# ESC.net
KiCad netlist of a schematic drawn in Altium Designer
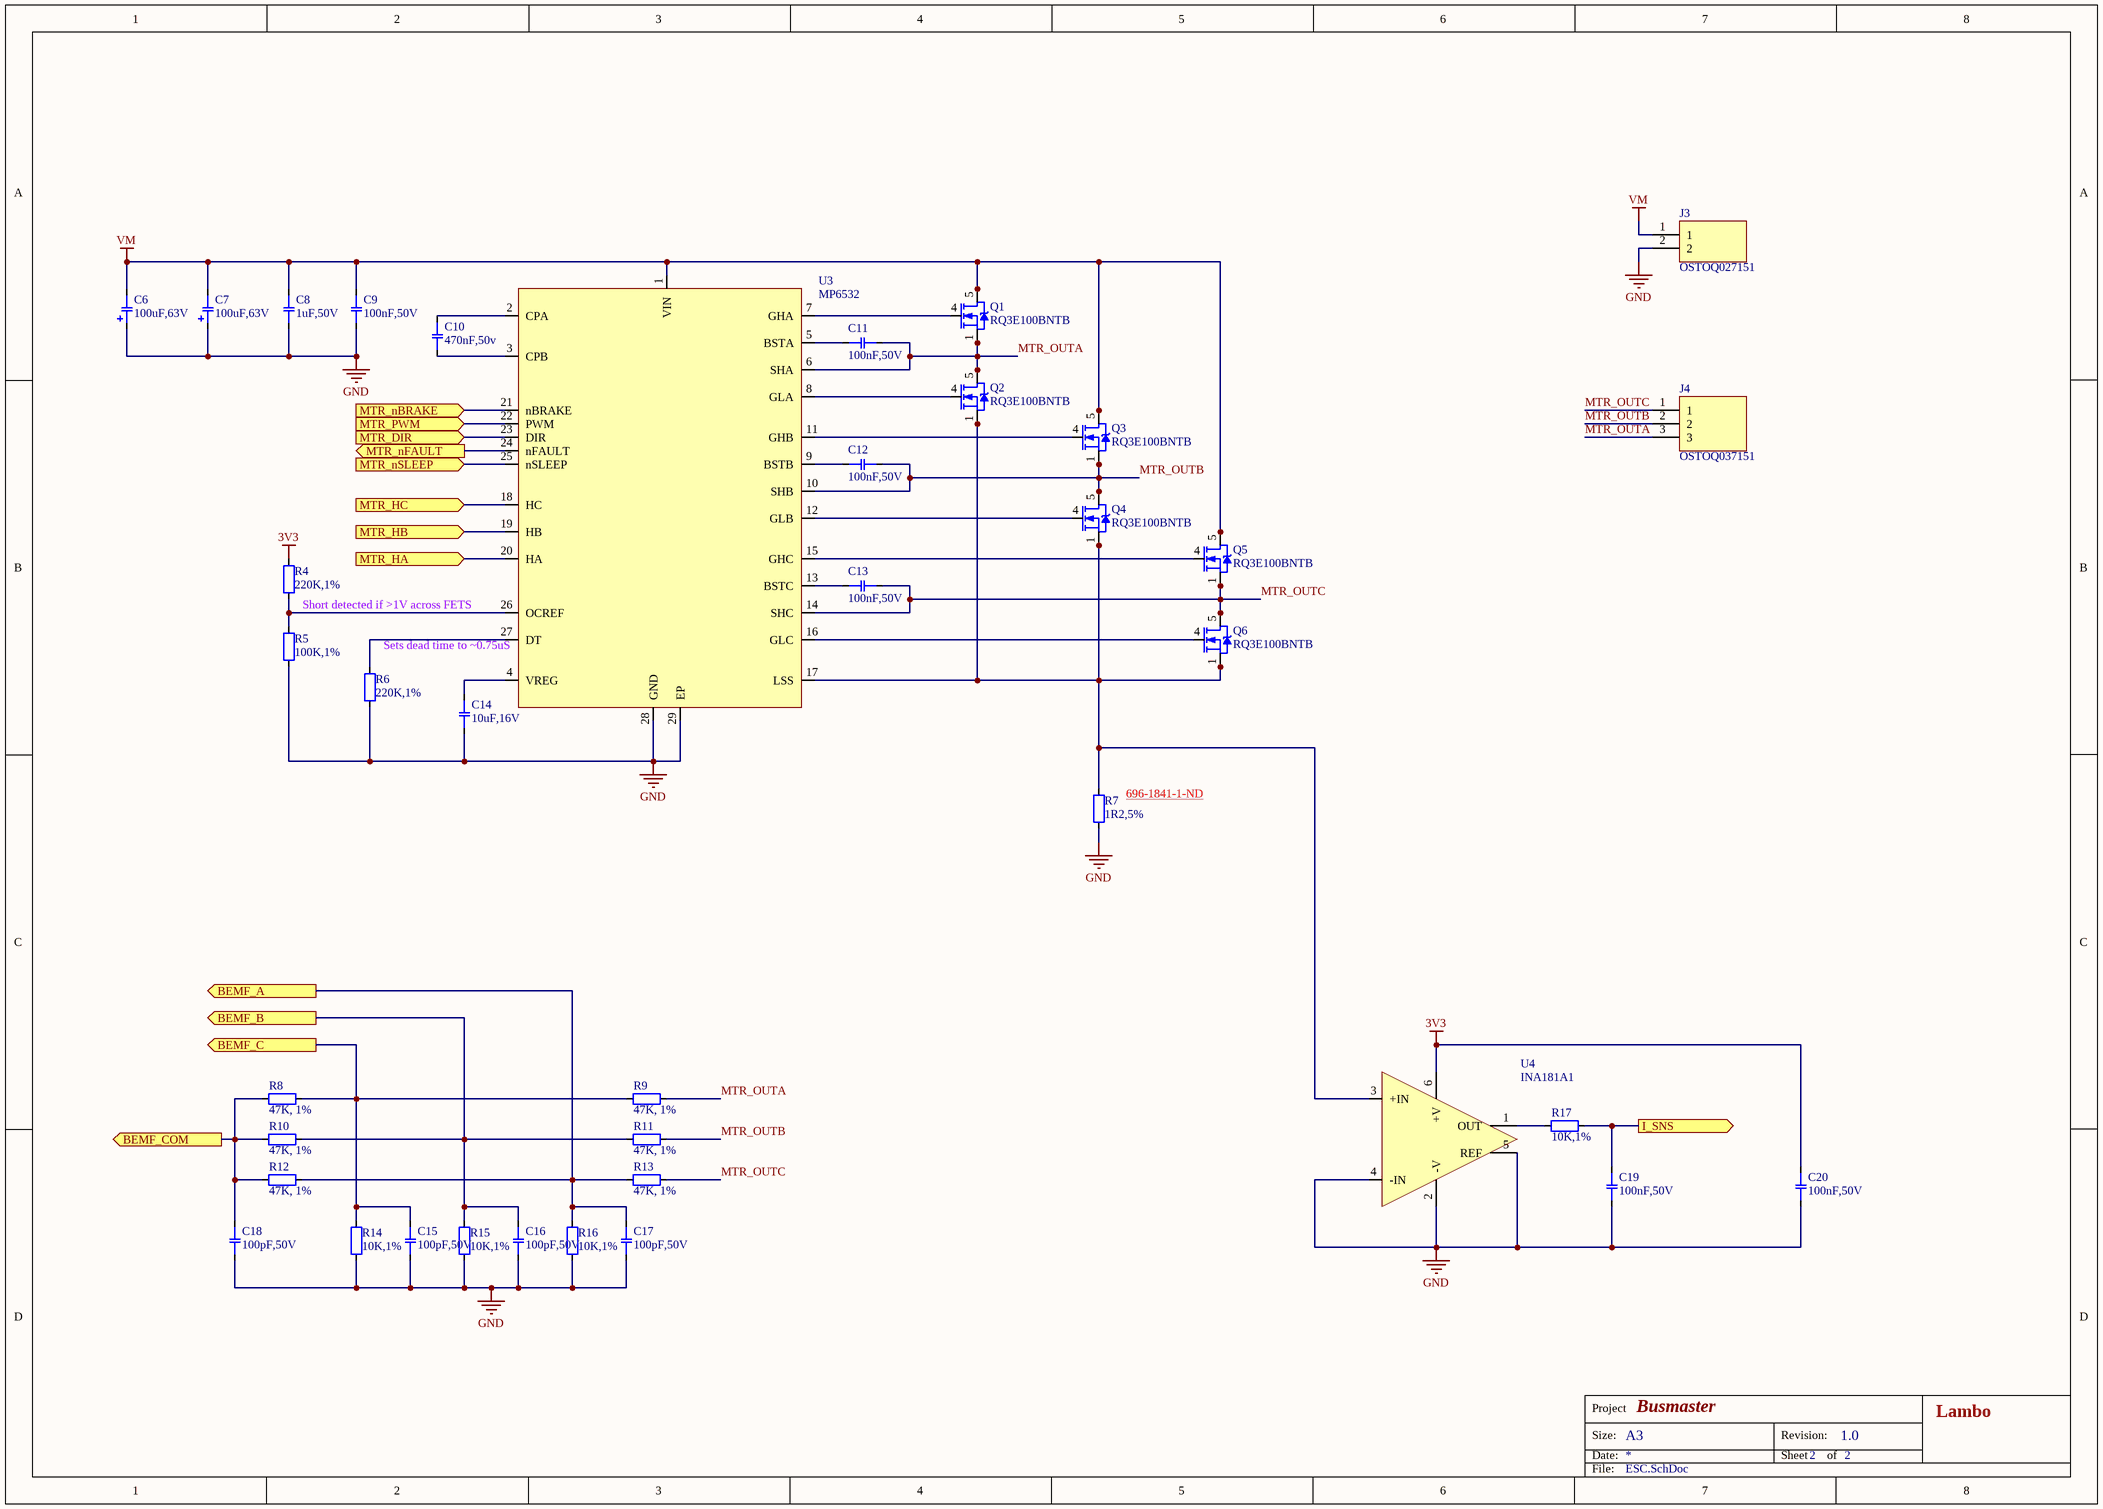
[diagram p0: ESC.SchDoc]

(export (version "E")
  (design (tool "Eeschema 10.0.6"))
  (components
    (comp (ref "C6")
      (value "100uF,63V")
      (footprint "CAPAE1030X1020N")
      (description "CAP ALUM 100UF 63V 20% SMD")
      (fields
        (field (name "MANUFACTURER") "Panasonic Electronic Components")
        (field (name "TOLERANCE") "20%")
      )
      (libsource (lib "library") (part "CAP-POL_1"))
    )
    (comp (ref "C7")
      (value "100uF,63V")
      (footprint "CAPAE1030X1020N")
      (description "CAP ALUM 100UF 63V 20% SMD")
      (fields
        (field (name "MANUFACTURER") "Panasonic Electronic Components")
        (field (name "TOLERANCE") "20%")
      )
      (libsource (lib "library") (part "CAP-POL_1"))
    )
    (comp (ref "C8")
      (value "1uF,50V")
      (footprint "CAPC1608X09N_0603")
      (description "AUTOMOTIVE CAP CER 1UF 50V 10% X5R 0603")
      (fields (field (name "MANUFACTURER") "TDK Corporation") (field (name "TOLERANCE") "10%"))
      (libsource (lib "library") (part "CAP-NP_1"))
    )
    (comp (ref "C9")
      (value "100nF,50V")
      (footprint "CAPC1608X09N_0603")
      (description "CAP CER 0.1UF 50V 10% X7R 0603")
      (fields (field (name "MANUFACTURER") "Kemet") (field (name "TOLERANCE") "10%"))
      (libsource (lib "library") (part "CAP-NP_1"))
    )
    (comp (ref "C10")
      (value "470nF,50v")
      (footprint "CAPC1608X09N_0603")
      (description "AUTOMOTIVE CAP CER 470nF 50V 10% X5R 0603")
      (fields (field (name "MANUFACTURER") "Taiyo Yuden") (field (name "TOLERANCE") "10%"))
      (libsource (lib "library") (part "CAP-NP_1"))
    )
    (comp (ref "C11")
      (value "100nF,50V")
      (footprint "CAPC1608X09N_0603")
      (description "CAP CER 0.1UF 50V 10% X7R 0603")
      (fields (field (name "MANUFACTURER") "Kemet") (field (name "TOLERANCE") "10%"))
      (libsource (lib "library") (part "CAP-NP_1"))
    )
    (comp (ref "C12")
      (value "100nF,50V")
      (footprint "CAPC1608X09N_0603")
      (description "CAP CER 0.1UF 50V 10% X7R 0603")
      (fields (field (name "MANUFACTURER") "Kemet") (field (name "TOLERANCE") "10%"))
      (libsource (lib "library") (part "CAP-NP_1"))
    )
    (comp (ref "C13")
      (value "100nF,50V")
      (footprint "CAPC1608X09N_0603")
      (description "CAP CER 0.1UF 50V 10% X7R 0603")
      (fields (field (name "MANUFACTURER") "Kemet") (field (name "TOLERANCE") "10%"))
      (libsource (lib "library") (part "CAP-NP_1"))
    )
    (comp (ref "C14")
      (value "10uF,16V")
      (footprint "CAPC2012X12N_0805")
      (description "CAP CER 10µF ±10% 16V X7R 0805")
      (fields
        (field (name "MANUFACTURER") "Samsung Electro-Mechanics America, Inc.")
        (field (name "TOLERANCE") "10%")
      )
      (libsource (lib "library") (part "CAP-NP_1"))
    )
    (comp (ref "C15")
      (value "100pF,50V")
      (footprint "CAPC1608X09N_0603")
      (description "CAP CER 100PF 50V 10% NP0 0603")
      (fields (field (name "MANUFACTURER") "AVX") (field (name "TOLERANCE") "10%"))
      (libsource (lib "library") (part "CAP-NP_1"))
    )
    (comp (ref "C16")
      (value "100pF,50V")
      (footprint "CAPC1608X09N_0603")
      (description "CAP CER 100PF 50V 10% NP0 0603")
      (fields (field (name "MANUFACTURER") "AVX") (field (name "TOLERANCE") "10%"))
      (libsource (lib "library") (part "CAP-NP_1"))
    )
    (comp (ref "C17")
      (value "100pF,50V")
      (footprint "CAPC1608X09N_0603")
      (description "CAP CER 100PF 50V 10% NP0 0603")
      (fields (field (name "MANUFACTURER") "AVX") (field (name "TOLERANCE") "10%"))
      (libsource (lib "library") (part "CAP-NP_1"))
    )
    (comp (ref "C18")
      (value "100pF,50V")
      (footprint "CAPC1608X09N_0603")
      (description "CAP CER 100PF 50V 10% NP0 0603")
      (fields (field (name "MANUFACTURER") "AVX") (field (name "TOLERANCE") "10%"))
      (libsource (lib "library") (part "CAP-NP_1"))
    )
    (comp (ref "C19")
      (value "100nF,50V")
      (footprint "CAPC1608X09N_0603")
      (description "CAP CER 0.1UF 50V 10% X7R 0603")
      (fields (field (name "MANUFACTURER") "Kemet") (field (name "TOLERANCE") "10%"))
      (libsource (lib "library") (part "CAP-NP_1"))
    )
    (comp (ref "C20")
      (value "100nF,50V")
      (footprint "CAPC1608X09N_0603")
      (description "CAP CER 0.1UF 50V 10% X7R 0603")
      (fields (field (name "MANUFACTURER") "Kemet") (field (name "TOLERANCE") "10%"))
      (libsource (lib "library") (part "CAP-NP_1"))
    )
    (comp (ref "J3")
      (value "OSTOQ027151")
      (footprint "ONSHORE_OSTOQ027151")
      (description "TERM BLOCK HDR 2POS R/A 5MM")
      (fields (field (name "MANUFACTURER") "On Shore Technology Inc"))
      (libsource (lib "library") (part "ONSHORE_OSTOQ027151"))
    )
    (comp (ref "J4")
      (value "OSTOQ037151")
      (footprint "ONSHORE_OSTOQ037151")
      (description "TERM BLOCK HDR 3POS R/A 5MM")
      (fields (field (name "MANUFACTURER") "On Shore Technology Inc"))
      (libsource (lib "library") (part "ONSHORE_OSTOQ037151"))
    )
    (comp (ref "Q1")
      (value "RQ3E100BNTB")
      (footprint "ROHM-HSMT8")
      (description "MOSFET N-CH 30V 10A 8HSMT")
      (fields (field (name "MANUFACTURER") "Rohm Semiconductor"))
      (libsource (lib "library") (part "MOSFET-N-QFN8"))
    )
    (comp (ref "Q2")
      (value "RQ3E100BNTB")
      (footprint "ROHM-HSMT8")
      (description "MOSFET N-CH 30V 10A 8HSMT")
      (fields (field (name "MANUFACTURER") "Rohm Semiconductor"))
      (libsource (lib "library") (part "MOSFET-N-QFN8"))
    )
    (comp (ref "Q3")
      (value "RQ3E100BNTB")
      (footprint "ROHM-HSMT8")
      (description "MOSFET N-CH 30V 10A 8HSMT")
      (fields (field (name "MANUFACTURER") "Rohm Semiconductor"))
      (libsource (lib "library") (part "MOSFET-N-QFN8"))
    )
    (comp (ref "Q4")
      (value "RQ3E100BNTB")
      (footprint "ROHM-HSMT8")
      (description "MOSFET N-CH 30V 10A 8HSMT")
      (fields (field (name "MANUFACTURER") "Rohm Semiconductor"))
      (libsource (lib "library") (part "MOSFET-N-QFN8"))
    )
    (comp (ref "Q5")
      (value "RQ3E100BNTB")
      (footprint "ROHM-HSMT8")
      (description "MOSFET N-CH 30V 10A 8HSMT")
      (fields (field (name "MANUFACTURER") "Rohm Semiconductor"))
      (libsource (lib "library") (part "MOSFET-N-QFN8"))
    )
    (comp (ref "Q6")
      (value "RQ3E100BNTB")
      (footprint "ROHM-HSMT8")
      (description "MOSFET N-CH 30V 10A 8HSMT")
      (fields (field (name "MANUFACTURER") "Rohm Semiconductor"))
      (libsource (lib "library") (part "MOSFET-N-QFN8"))
    )
    (comp (ref "R4")
      (value "220K,1%")
      (footprint "RESC1608X06N_0603")
      (description "RES 220K OHM 1/10W 1% 0603 SMD")
      (fields (field (name "MANUFACTURER") "Yageo") (field (name "POWER") "0.1W"))
      (libsource (lib "library") (part "RESISTOR_1"))
    )
    (comp (ref "R5")
      (value "100K,1%")
      (footprint "RESC1608X06N_0603")
      (description "RES 100K OHM 1/10W 1% 0603 SMD")
      (fields (field (name "MANUFACTURER") "Yageo") (field (name "POWER") "0.1W"))
      (libsource (lib "library") (part "RESISTOR_1"))
    )
    (comp (ref "R6")
      (value "220K,1%")
      (footprint "RESC1608X06N_0603")
      (description "RES 220K OHM 1/10W 1% 0603 SMD")
      (fields (field (name "MANUFACTURER") "Yageo") (field (name "POWER") "0.1W"))
      (libsource (lib "library") (part "RESISTOR_1"))
    )
    (comp (ref "R7")
      (value "1R2,5%")
      (footprint "RESC6432X07N_2512")
      (description "RES SMD 1.2 OHM 5% 3W 2512")
      (fields (field (name "MANUFACTURER") "TE Connectivity Passive Product") (field (name "POWER") "3W"))
      (libsource (lib "library") (part "RESISTOR_1"))
    )
    (comp (ref "R8")
      (value "47K, 1%")
      (footprint "RESC1608X06N_0603")
      (description "AUTOMOTIVE RES 47.0K OHM 1/10W 1% 0603 SMD")
      (fields (field (name "MANUFACTURER") "Vishay Dale") (field (name "POWER") "0.1W"))
      (libsource (lib "") (part "RESISTOR_1_1"))
    )
    (comp (ref "R9")
      (value "47K, 1%")
      (footprint "RESC1608X06N_0603")
      (description "AUTOMOTIVE RES 47.0K OHM 1/10W 1% 0603 SMD")
      (fields (field (name "MANUFACTURER") "Vishay Dale") (field (name "POWER") "0.1W"))
      (libsource (lib "") (part "RESISTOR_1_1"))
    )
    (comp (ref "R10")
      (value "47K, 1%")
      (footprint "RESC1608X06N_0603")
      (description "AUTOMOTIVE RES 47.0K OHM 1/10W 1% 0603 SMD")
      (fields (field (name "MANUFACTURER") "Vishay Dale") (field (name "POWER") "0.1W"))
      (libsource (lib "") (part "RESISTOR_1_1"))
    )
    (comp (ref "R11")
      (value "47K, 1%")
      (footprint "RESC1608X06N_0603")
      (description "AUTOMOTIVE RES 47.0K OHM 1/10W 1% 0603 SMD")
      (fields (field (name "MANUFACTURER") "Vishay Dale") (field (name "POWER") "0.1W"))
      (libsource (lib "") (part "RESISTOR_1_1"))
    )
    (comp (ref "R12")
      (value "47K, 1%")
      (footprint "RESC1608X06N_0603")
      (description "AUTOMOTIVE RES 47.0K OHM 1/10W 1% 0603 SMD")
      (fields (field (name "MANUFACTURER") "Vishay Dale") (field (name "POWER") "0.1W"))
      (libsource (lib "") (part "RESISTOR_1_1"))
    )
    (comp (ref "R13")
      (value "47K, 1%")
      (footprint "RESC1608X06N_0603")
      (description "AUTOMOTIVE RES 47.0K OHM 1/10W 1% 0603 SMD")
      (fields (field (name "MANUFACTURER") "Vishay Dale") (field (name "POWER") "0.1W"))
      (libsource (lib "") (part "RESISTOR_1_1"))
    )
    (comp (ref "R14")
      (value "10K,1%")
      (footprint "RESC1608X06N_0603")
      (description "RES 10.0K OHM 1/10W 1% 0603 SMD")
      (fields (field (name "MANUFACTURER") "Yageo") (field (name "POWER") "0.1W"))
      (libsource (lib "") (part "RESISTOR_1_2"))
    )
    (comp (ref "R15")
      (value "10K,1%")
      (footprint "RESC1608X06N_0603")
      (description "RES 10.0K OHM 1/10W 1% 0603 SMD")
      (fields (field (name "MANUFACTURER") "Yageo") (field (name "POWER") "0.1W"))
      (libsource (lib "") (part "RESISTOR_1_2"))
    )
    (comp (ref "R16")
      (value "10K,1%")
      (footprint "RESC1608X06N_0603")
      (description "RES 10.0K OHM 1/10W 1% 0603 SMD")
      (fields (field (name "MANUFACTURER") "Yageo") (field (name "POWER") "0.1W"))
      (libsource (lib "") (part "RESISTOR_1_2"))
    )
    (comp (ref "R17")
      (value "10K,1%")
      (footprint "RESC1608X06N_0603")
      (description "RES 10.0K OHM 1/10W 1% 0603 SMD")
      (fields (field (name "MANUFACTURER") "Yageo") (field (name "POWER") "0.1W"))
      (libsource (lib "") (part "RESISTOR_1_3"))
    )
    (comp (ref "U3")
      (value "MP6532")
      (footprint "QFN40P400X400X100-28N_28QFN")
      (description "IC MOTOR DRIVER 5V-60V 28QFN")
      (fields
        (field (name "MANUFACTURER") "Monolithic Power Systems Inc.")
        (field (name "MANUFACTURER PART NUMBER") "MP6532-GR-Z")
      )
      (libsource (lib "library") (part "MP6532"))
    )
    (comp (ref "U4")
      (value "INA181A1")
      (footprint "SOT95P280X145-6N_SOT23-6")
      (description "IC AMP CUR SENSE 350KHZ SOT23-6")
      (fields
        (field (name "MANUFACTURER") "Texas Instruments")
        (field (name "MANUFACTURER PART NUMBER") "INA181A1IDBVT")
      )
      (libsource (lib "library") (part "INA181AX"))
    )
  )
  (nets
    (net (code "1") (name "/BEMF_A") (class "Default")
      (node (ref "C17") (pin "2") (pinfunction "2_2") (pintype "passive"))
      (node (ref "R12") (pin "2") (pinfunction "2_2") (pintype "passive"))
      (node (ref "R13") (pin "1") (pinfunction "1_1") (pintype "passive"))
      (node (ref "R16") (pin "1") (pinfunction "1_1") (pintype "passive"))
    )
    (net (code "2") (name "/BEMF_B") (class "Default")
      (node (ref "C16") (pin "2") (pinfunction "2_2") (pintype "passive"))
      (node (ref "R10") (pin "2") (pinfunction "2_2") (pintype "passive"))
      (node (ref "R11") (pin "1") (pinfunction "1_1") (pintype "passive"))
      (node (ref "R15") (pin "1") (pinfunction "1_1") (pintype "passive"))
    )
    (net (code "3") (name "/BEMF_C") (class "Default")
      (node (ref "C15") (pin "2") (pinfunction "2_2") (pintype "passive"))
      (node (ref "R14") (pin "1") (pinfunction "1_1") (pintype "passive"))
      (node (ref "R8") (pin "2") (pinfunction "2_2") (pintype "passive"))
      (node (ref "R9") (pin "1") (pinfunction "1_1") (pintype "passive"))
    )
    (net (code "4") (name "/BEMF_COM") (class "Default")
      (node (ref "C18") (pin "2") (pinfunction "2_2") (pintype "passive"))
      (node (ref "R10") (pin "1") (pinfunction "1_1") (pintype "passive"))
      (node (ref "R12") (pin "1") (pinfunction "1_1") (pintype "passive"))
      (node (ref "R8") (pin "1") (pinfunction "1_1") (pintype "passive"))
    )
    (net (code "5") (name "/I_SNS") (class "Default")
      (node (ref "C19") (pin "1") (pinfunction "1_1") (pintype "passive"))
      (node (ref "R17") (pin "1") (pinfunction "1_1") (pintype "passive"))
    )
    (net (code "6") (name "/MTR_DIR") (class "Default")
      (node (ref "U3") (pin "23") (pinfunction "DIR_23") (pintype "passive"))
    )
    (net (code "7") (name "/MTR_HA") (class "Default")
      (node (ref "U3") (pin "20") (pinfunction "HA_20") (pintype "passive"))
    )
    (net (code "8") (name "/MTR_HB") (class "Default")
      (node (ref "U3") (pin "19") (pinfunction "HB_19") (pintype "passive"))
    )
    (net (code "9") (name "/MTR_HC") (class "Default")
      (node (ref "U3") (pin "18") (pinfunction "HC_18") (pintype "passive"))
    )
    (net (code "10") (name "/MTR_OUTA") (class "Default")
      (node (ref "C11") (pin "1") (pinfunction "1_1") (pintype "passive"))
      (node (ref "J4") (pin "3") (pinfunction "3_3") (pintype "passive"))
      (node (ref "Q1") (pin "1") (pinfunction "S_1") (pintype "passive"))
      (node (ref "Q1") (pin "2") (pinfunction "S_2") (pintype "passive"))
      (node (ref "Q1") (pin "3") (pinfunction "S_3") (pintype "passive"))
      (node (ref "Q2") (pin "5") (pinfunction "D_5") (pintype "passive"))
      (node (ref "Q2") (pin "6") (pinfunction "D_6") (pintype "passive"))
      (node (ref "Q2") (pin "7") (pinfunction "D_7") (pintype "passive"))
      (node (ref "Q2") (pin "8") (pinfunction "D_8") (pintype "passive"))
      (node (ref "R9") (pin "2") (pinfunction "2_2") (pintype "passive"))
      (node (ref "U3") (pin "6") (pinfunction "SHA_6") (pintype "passive"))
    )
    (net (code "11") (name "/MTR_OUTB") (class "Default")
      (node (ref "C12") (pin "1") (pinfunction "1_1") (pintype "passive"))
      (node (ref "J4") (pin "2") (pinfunction "2_2") (pintype "passive"))
      (node (ref "Q3") (pin "1") (pinfunction "S_1") (pintype "passive"))
      (node (ref "Q3") (pin "2") (pinfunction "S_2") (pintype "passive"))
      (node (ref "Q3") (pin "3") (pinfunction "S_3") (pintype "passive"))
      (node (ref "Q4") (pin "5") (pinfunction "D_5") (pintype "passive"))
      (node (ref "Q4") (pin "6") (pinfunction "D_6") (pintype "passive"))
      (node (ref "Q4") (pin "7") (pinfunction "D_7") (pintype "passive"))
      (node (ref "Q4") (pin "8") (pinfunction "D_8") (pintype "passive"))
      (node (ref "R11") (pin "2") (pinfunction "2_2") (pintype "passive"))
      (node (ref "U3") (pin "10") (pinfunction "SHB_10") (pintype "passive"))
    )
    (net (code "12") (name "/MTR_OUTC") (class "Default")
      (node (ref "C13") (pin "1") (pinfunction "1_1") (pintype "passive"))
      (node (ref "J4") (pin "1") (pinfunction "1_1") (pintype "passive"))
      (node (ref "Q5") (pin "1") (pinfunction "S_1") (pintype "passive"))
      (node (ref "Q5") (pin "2") (pinfunction "S_2") (pintype "passive"))
      (node (ref "Q5") (pin "3") (pinfunction "S_3") (pintype "passive"))
      (node (ref "Q6") (pin "5") (pinfunction "D_5") (pintype "passive"))
      (node (ref "Q6") (pin "6") (pinfunction "D_6") (pintype "passive"))
      (node (ref "Q6") (pin "7") (pinfunction "D_7") (pintype "passive"))
      (node (ref "Q6") (pin "8") (pinfunction "D_8") (pintype "passive"))
      (node (ref "R13") (pin "2") (pinfunction "2_2") (pintype "passive"))
      (node (ref "U3") (pin "14") (pinfunction "SHC_14") (pintype "passive"))
    )
    (net (code "13") (name "/MTR_PWM") (class "Default")
      (node (ref "U3") (pin "22") (pinfunction "PWM_22") (pintype "passive"))
    )
    (net (code "14") (name "/MTR_nBRAKE") (class "Default")
      (node (ref "U3") (pin "21") (pinfunction "nBRAKE_21") (pintype "passive"))
    )
    (net (code "15") (name "/MTR_nFAULT") (class "Default")
      (node (ref "U3") (pin "24") (pinfunction "nFAULT_24") (pintype "passive"))
    )
    (net (code "16") (name "/MTR_nSLEEP") (class "Default")
      (node (ref "U3") (pin "25") (pinfunction "nSLEEP_25") (pintype "passive"))
    )
    (net (code "17") (name "3V3") (class "Default")
      (node (ref "C20") (pin "1") (pinfunction "1_1") (pintype "passive"))
      (node (ref "R4") (pin "2") (pinfunction "2_2") (pintype "passive"))
      (node (ref "U4") (pin "6") (pinfunction "+V_6") (pintype "passive"))
    )
    (net (code "18") (name "GND") (class "Default")
      (node (ref "C14") (pin "1") (pinfunction "1_1") (pintype "passive"))
      (node (ref "C15") (pin "1") (pinfunction "1_1") (pintype "passive"))
      (node (ref "C16") (pin "1") (pinfunction "1_1") (pintype "passive"))
      (node (ref "C17") (pin "1") (pinfunction "1_1") (pintype "passive"))
      (node (ref "C18") (pin "1") (pinfunction "1_1") (pintype "passive"))
      (node (ref "C19") (pin "2") (pinfunction "2_2") (pintype "passive"))
      (node (ref "C20") (pin "2") (pinfunction "2_2") (pintype "passive"))
      (node (ref "C6") (pin "1") (pinfunction "+_1") (pintype "passive"))
      (node (ref "C7") (pin "1") (pinfunction "+_1") (pintype "passive"))
      (node (ref "C8") (pin "1") (pinfunction "1_1") (pintype "passive"))
      (node (ref "C9") (pin "2") (pinfunction "2_2") (pintype "passive"))
      (node (ref "J3") (pin "2") (pinfunction "2_2") (pintype "passive"))
      (node (ref "R14") (pin "2") (pinfunction "2_2") (pintype "passive"))
      (node (ref "R15") (pin "2") (pinfunction "2_2") (pintype "passive"))
      (node (ref "R16") (pin "2") (pinfunction "2_2") (pintype "passive"))
      (node (ref "R5") (pin "1") (pinfunction "1_1") (pintype "passive"))
      (node (ref "R6") (pin "1") (pinfunction "1_1") (pintype "passive"))
      (node (ref "R7") (pin "1") (pinfunction "1_1") (pintype "passive"))
      (node (ref "U3") (pin "28") (pinfunction "GND_28") (pintype "passive"))
      (node (ref "U3") (pin "29") (pinfunction "EP_29") (pintype "passive"))
      (node (ref "U4") (pin "2") (pinfunction "-V_2") (pintype "passive"))
      (node (ref "U4") (pin "4") (pinfunction "-IN_4") (pintype "passive"))
      (node (ref "U4") (pin "5") (pinfunction "REF_5") (pintype "passive"))
    )
    (net (code "19") (name "Net-(Q1-G)") (class "Default")
      (node (ref "Q1") (pin "4") (pinfunction "G_4") (pintype "passive"))
      (node (ref "U3") (pin "7") (pinfunction "GHA_7") (pintype "passive"))
    )
    (net (code "20") (name "Net-(Q2-G)") (class "Default")
      (node (ref "Q2") (pin "4") (pinfunction "G_4") (pintype "passive"))
      (node (ref "U3") (pin "8") (pinfunction "GLA_8") (pintype "passive"))
    )
    (net (code "21") (name "Net-(Q3-G)") (class "Default")
      (node (ref "Q3") (pin "4") (pinfunction "G_4") (pintype "passive"))
      (node (ref "U3") (pin "11") (pinfunction "GHB_11") (pintype "passive"))
    )
    (net (code "22") (name "Net-(Q4-G)") (class "Default")
      (node (ref "Q4") (pin "4") (pinfunction "G_4") (pintype "passive"))
      (node (ref "U3") (pin "12") (pinfunction "GLB_12") (pintype "passive"))
    )
    (net (code "23") (name "Net-(Q5-G)") (class "Default")
      (node (ref "Q5") (pin "4") (pinfunction "G_4") (pintype "passive"))
      (node (ref "U3") (pin "15") (pinfunction "GHC_15") (pintype "passive"))
    )
    (net (code "24") (name "Net-(Q6-G)") (class "Default")
      (node (ref "Q6") (pin "4") (pinfunction "G_4") (pintype "passive"))
      (node (ref "U3") (pin "16") (pinfunction "GLC_16") (pintype "passive"))
    )
    (net (code "25") (name "Net-(U3-BSTA)") (class "Default")
      (node (ref "C11") (pin "2") (pinfunction "2_2") (pintype "passive"))
      (node (ref "U3") (pin "5") (pinfunction "BSTA_5") (pintype "passive"))
    )
    (net (code "26") (name "Net-(U3-BSTB)") (class "Default")
      (node (ref "C12") (pin "2") (pinfunction "2_2") (pintype "passive"))
      (node (ref "U3") (pin "9") (pinfunction "BSTB_9") (pintype "passive"))
    )
    (net (code "27") (name "Net-(U3-BSTC)") (class "Default")
      (node (ref "C13") (pin "2") (pinfunction "2_2") (pintype "passive"))
      (node (ref "U3") (pin "13") (pinfunction "BSTC_13") (pintype "passive"))
    )
    (net (code "28") (name "Net-(U3-CPA)") (class "Default")
      (node (ref "C10") (pin "2") (pinfunction "2_2") (pintype "passive"))
      (node (ref "U3") (pin "2") (pinfunction "CPA_2") (pintype "passive"))
    )
    (net (code "29") (name "Net-(U3-CPB)") (class "Default")
      (node (ref "C10") (pin "1") (pinfunction "1_1") (pintype "passive"))
      (node (ref "U3") (pin "3") (pinfunction "CPB_3") (pintype "passive"))
    )
    (net (code "30") (name "Net-(U3-DT)") (class "Default")
      (node (ref "R6") (pin "2") (pinfunction "2_2") (pintype "passive"))
      (node (ref "U3") (pin "27") (pinfunction "DT_27") (pintype "passive"))
    )
    (net (code "31") (name "Net-(U3-LSS)") (class "Default")
      (node (ref "Q2") (pin "1") (pinfunction "S_1") (pintype "passive"))
      (node (ref "Q2") (pin "2") (pinfunction "S_2") (pintype "passive"))
      (node (ref "Q2") (pin "3") (pinfunction "S_3") (pintype "passive"))
      (node (ref "Q4") (pin "1") (pinfunction "S_1") (pintype "passive"))
      (node (ref "Q4") (pin "2") (pinfunction "S_2") (pintype "passive"))
      (node (ref "Q4") (pin "3") (pinfunction "S_3") (pintype "passive"))
      (node (ref "Q6") (pin "1") (pinfunction "S_1") (pintype "passive"))
      (node (ref "Q6") (pin "2") (pinfunction "S_2") (pintype "passive"))
      (node (ref "Q6") (pin "3") (pinfunction "S_3") (pintype "passive"))
      (node (ref "R7") (pin "2") (pinfunction "2_2") (pintype "passive"))
      (node (ref "U3") (pin "17") (pinfunction "LSS_17") (pintype "passive"))
      (node (ref "U4") (pin "3") (pinfunction "+IN_3") (pintype "passive"))
    )
    (net (code "32") (name "Net-(U3-OCREF)") (class "Default")
      (node (ref "R4") (pin "1") (pinfunction "1_1") (pintype "passive"))
      (node (ref "R5") (pin "2") (pinfunction "2_2") (pintype "passive"))
      (node (ref "U3") (pin "26") (pinfunction "OCREF_26") (pintype "passive"))
    )
    (net (code "33") (name "Net-(U3-VREG)") (class "Default")
      (node (ref "C14") (pin "2") (pinfunction "2_2") (pintype "passive"))
      (node (ref "U3") (pin "4") (pinfunction "VREG_4") (pintype "passive"))
    )
    (net (code "34") (name "Net-(U4-OUT)") (class "Default")
      (node (ref "R17") (pin "2") (pinfunction "2_2") (pintype "passive"))
      (node (ref "U4") (pin "1") (pinfunction "OUT_1") (pintype "passive"))
    )
    (net (code "35") (name "VM") (class "Default")
      (node (ref "C6") (pin "2") (pinfunction "-_2") (pintype "passive"))
      (node (ref "C7") (pin "2") (pinfunction "-_2") (pintype "passive"))
      (node (ref "C8") (pin "2") (pinfunction "2_2") (pintype "passive"))
      (node (ref "C9") (pin "1") (pinfunction "1_1") (pintype "passive"))
      (node (ref "J3") (pin "1") (pinfunction "1_1") (pintype "passive"))
      (node (ref "Q1") (pin "5") (pinfunction "D_5") (pintype "passive"))
      (node (ref "Q1") (pin "6") (pinfunction "D_6") (pintype "passive"))
      (node (ref "Q1") (pin "7") (pinfunction "D_7") (pintype "passive"))
      (node (ref "Q1") (pin "8") (pinfunction "D_8") (pintype "passive"))
      (node (ref "Q3") (pin "5") (pinfunction "D_5") (pintype "passive"))
      (node (ref "Q3") (pin "6") (pinfunction "D_6") (pintype "passive"))
      (node (ref "Q3") (pin "7") (pinfunction "D_7") (pintype "passive"))
      (node (ref "Q3") (pin "8") (pinfunction "D_8") (pintype "passive"))
      (node (ref "Q5") (pin "5") (pinfunction "D_5") (pintype "passive"))
      (node (ref "Q5") (pin "6") (pinfunction "D_6") (pintype "passive"))
      (node (ref "Q5") (pin "7") (pinfunction "D_7") (pintype "passive"))
      (node (ref "Q5") (pin "8") (pinfunction "D_8") (pintype "passive"))
      (node (ref "U3") (pin "1") (pinfunction "VIN_1") (pintype "passive"))
    )
  )
)
